# Curvetracer-Mk1.net
KiCad netlist of a schematic drawn in EAGLE
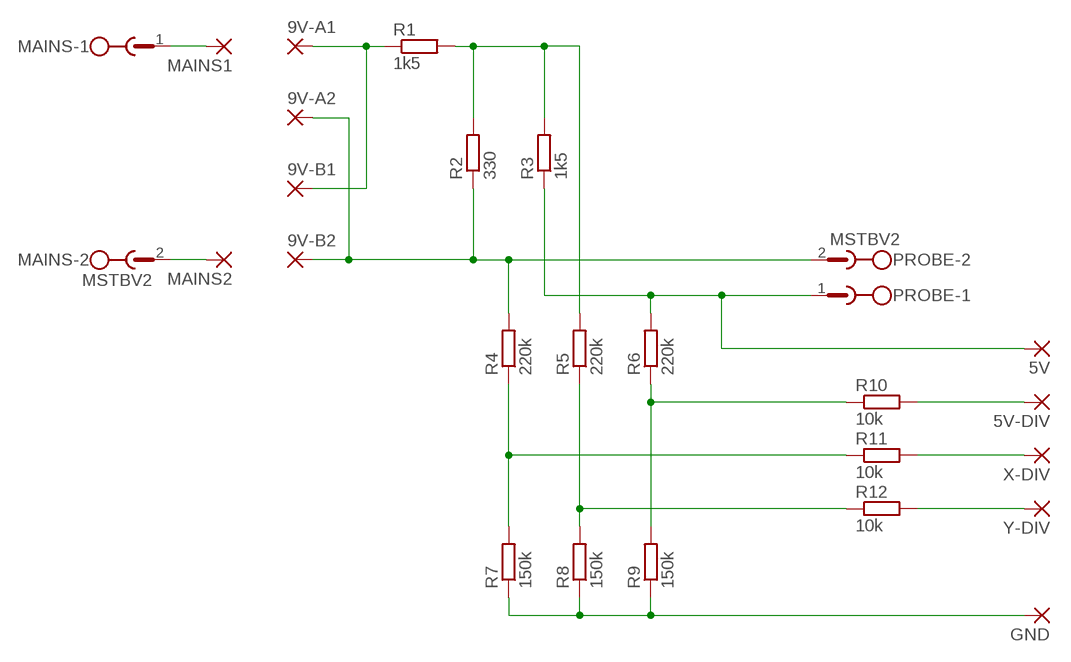
[diagram p0: schematic, sheet 1]

(export (version "E")
  (design (tool "Eeschema 10.0.6"))
  (components
    (comp (ref "5V")
      (value "2,15/1,0")
      (footprint "eagle-import:2,15_1,0")
      (libsource (lib "eagle-import") (part "2,15/1,0"))
    )
    (comp (ref "5V-DIV")
      (value "2,15/1,0")
      (footprint "eagle-import:2,15_1,0")
      (libsource (lib "eagle-import") (part "2,15/1,0"))
    )
    (comp (ref "9V-A1")
      (value "2,15/1,0")
      (footprint "eagle-import:2,15_1,0")
      (libsource (lib "eagle-import") (part "2,15/1,0"))
    )
    (comp (ref "9V-A2")
      (value "2,15/1,0")
      (footprint "eagle-import:2,15_1,0")
      (libsource (lib "eagle-import") (part "2,15/1,0"))
    )
    (comp (ref "9V-B1")
      (value "2,15/1,0")
      (footprint "eagle-import:2,15_1,0")
      (libsource (lib "eagle-import") (part "2,15/1,0"))
    )
    (comp (ref "9V-B2")
      (value "2,15/1,0")
      (footprint "eagle-import:2,15_1,0")
      (libsource (lib "eagle-import") (part "2,15/1,0"))
    )
    (comp (ref "GND")
      (value "2,15/1,0")
      (footprint "eagle-import:2,15_1,0")
      (libsource (lib "eagle-import") (part "2,15/1,0"))
    )
    (comp (ref "MAINS")
      (value "MSTBV2")
      (footprint "eagle-import:MSTBV2")
      (fields (field (name "MPN") "MSTBV 2,5/2-GF-5.08"))
      (libsource (lib "eagle-import") (part "MSTBV2"))
    )
    (comp (ref "MAINS1")
      (value "2,15/1,0")
      (footprint "eagle-import:2,15_1,0")
      (libsource (lib "eagle-import") (part "2,15/1,0"))
    )
    (comp (ref "MAINS2")
      (value "2,15/1,0")
      (footprint "eagle-import:2,15_1,0")
      (libsource (lib "eagle-import") (part "2,15/1,0"))
    )
    (comp (ref "PROBE")
      (value "MSTBV2")
      (footprint "eagle-import:MSTBV2")
      (fields (field (name "MPN") "MSTBV 2,5/2-GF-5.08"))
      (libsource (lib "eagle-import") (part "MSTBV2"))
    )
    (comp (ref "R1")
      (value "1k5")
      (footprint "eagle-import:M0805")
      (libsource (lib "eagle-import") (part "R-EU_M0805"))
    )
    (comp (ref "R2")
      (value "330")
      (footprint "eagle-import:M0805")
      (libsource (lib "eagle-import") (part "R-EU_M0805"))
    )
    (comp (ref "R3")
      (value "1k5")
      (footprint "eagle-import:M0805")
      (libsource (lib "eagle-import") (part "R-EU_M0805"))
    )
    (comp (ref "R4")
      (value "220k")
      (footprint "eagle-import:M0805")
      (libsource (lib "eagle-import") (part "R-EU_M0805"))
    )
    (comp (ref "R5")
      (value "220k")
      (footprint "eagle-import:M0805")
      (libsource (lib "eagle-import") (part "R-EU_M0805"))
    )
    (comp (ref "R6")
      (value "220k")
      (footprint "eagle-import:M0805")
      (libsource (lib "eagle-import") (part "R-EU_M0805"))
    )
    (comp (ref "R7")
      (value "150k")
      (footprint "eagle-import:M0805")
      (libsource (lib "eagle-import") (part "R-EU_M0805"))
    )
    (comp (ref "R8")
      (value "150k")
      (footprint "eagle-import:M0805")
      (libsource (lib "eagle-import") (part "R-EU_M0805"))
    )
    (comp (ref "R9")
      (value "150k")
      (footprint "eagle-import:M0805")
      (libsource (lib "eagle-import") (part "R-EU_M0805"))
    )
    (comp (ref "R10")
      (value "10k")
      (footprint "eagle-import:M0805")
      (libsource (lib "eagle-import") (part "R-EU_M0805"))
    )
    (comp (ref "R11")
      (value "10k")
      (footprint "eagle-import:M0805")
      (libsource (lib "eagle-import") (part "R-EU_M0805"))
    )
    (comp (ref "R12")
      (value "10k")
      (footprint "eagle-import:M0805")
      (libsource (lib "eagle-import") (part "R-EU_M0805"))
    )
    (comp (ref "X-DIV")
      (value "2,15/1,0")
      (footprint "eagle-import:2,15_1,0")
      (libsource (lib "eagle-import") (part "2,15/1,0"))
    )
    (comp (ref "Y-DIV")
      (value "2,15/1,0")
      (footprint "eagle-import:2,15_1,0")
      (libsource (lib "eagle-import") (part "2,15/1,0"))
    )
  )
  (nets
    (net (code "1") (name "Net-(5V-DIV-P)") (class "Default")
      (node (ref "5V-DIV") (pin "1") (pinfunction "P_1") (pintype "passive"))
      (node (ref "R10") (pin "2") (pinfunction "2_2") (pintype "passive"))
    )
    (net (code "2") (name "Net-(5V-P)") (class "Default")
      (node (ref "5V") (pin "1") (pinfunction "P_1") (pintype "passive"))
      (node (ref "PROBE") (pin "1") (pinfunction "1_1") (pintype "passive"))
      (node (ref "R3") (pin "1") (pinfunction "1_1") (pintype "passive"))
      (node (ref "R6") (pin "2") (pinfunction "2_2") (pintype "passive"))
    )
    (net (code "3") (name "Net-(9V-A1-P)") (class "Default")
      (node (ref "9V-A1") (pin "1") (pinfunction "P_1") (pintype "passive"))
      (node (ref "9V-B1") (pin "1") (pinfunction "P_1") (pintype "passive"))
      (node (ref "R1") (pin "1") (pinfunction "1_1") (pintype "passive"))
    )
    (net (code "4") (name "Net-(9V-A2-P)") (class "Default")
      (node (ref "9V-A2") (pin "1") (pinfunction "P_1") (pintype "passive"))
      (node (ref "9V-B2") (pin "1") (pinfunction "P_1") (pintype "passive"))
      (node (ref "PROBE") (pin "2") (pinfunction "1_2") (pintype "passive"))
      (node (ref "R2") (pin "1") (pinfunction "1_1") (pintype "passive"))
      (node (ref "R4") (pin "2") (pinfunction "2_2") (pintype "passive"))
    )
    (net (code "5") (name "Net-(GND-P)") (class "Default")
      (node (ref "GND") (pin "1") (pinfunction "P_1") (pintype "passive"))
      (node (ref "R7") (pin "1") (pinfunction "1_1") (pintype "passive"))
      (node (ref "R8") (pin "1") (pinfunction "1_1") (pintype "passive"))
      (node (ref "R9") (pin "1") (pinfunction "1_1") (pintype "passive"))
    )
    (net (code "6") (name "Net-(MAINS1-P)") (class "Default")
      (node (ref "MAINS") (pin "1") (pinfunction "1_1") (pintype "passive"))
      (node (ref "MAINS1") (pin "1") (pinfunction "P_1") (pintype "passive"))
    )
    (net (code "7") (name "Net-(MAINS2-P)") (class "Default")
      (node (ref "MAINS") (pin "2") (pinfunction "1_2") (pintype "passive"))
      (node (ref "MAINS2") (pin "1") (pinfunction "P_1") (pintype "passive"))
    )
    (net (code "8") (name "Net-(R1-Pad2)") (class "Default")
      (node (ref "R1") (pin "2") (pinfunction "2_2") (pintype "passive"))
      (node (ref "R2") (pin "2") (pinfunction "2_2") (pintype "passive"))
      (node (ref "R3") (pin "2") (pinfunction "2_2") (pintype "passive"))
      (node (ref "R5") (pin "2") (pinfunction "2_2") (pintype "passive"))
    )
    (net (code "9") (name "Net-(R10-Pad1)") (class "Default")
      (node (ref "R10") (pin "1") (pinfunction "1_1") (pintype "passive"))
      (node (ref "R6") (pin "1") (pinfunction "1_1") (pintype "passive"))
      (node (ref "R9") (pin "2") (pinfunction "2_2") (pintype "passive"))
    )
    (net (code "10") (name "Net-(R11-Pad1)") (class "Default")
      (node (ref "R11") (pin "1") (pinfunction "1_1") (pintype "passive"))
      (node (ref "R4") (pin "1") (pinfunction "1_1") (pintype "passive"))
      (node (ref "R7") (pin "2") (pinfunction "2_2") (pintype "passive"))
    )
    (net (code "11") (name "Net-(R12-Pad1)") (class "Default")
      (node (ref "R12") (pin "1") (pinfunction "1_1") (pintype "passive"))
      (node (ref "R5") (pin "1") (pinfunction "1_1") (pintype "passive"))
      (node (ref "R8") (pin "2") (pinfunction "2_2") (pintype "passive"))
    )
    (net (code "12") (name "Net-(X-DIV-P)") (class "Default")
      (node (ref "R11") (pin "2") (pinfunction "2_2") (pintype "passive"))
      (node (ref "X-DIV") (pin "1") (pinfunction "P_1") (pintype "passive"))
    )
    (net (code "13") (name "Net-(Y-DIV-P)") (class "Default")
      (node (ref "R12") (pin "2") (pinfunction "2_2") (pintype "passive"))
      (node (ref "Y-DIV") (pin "1") (pinfunction "P_1") (pintype "passive"))
    )
  )
)
